# SH3_-_CONNECTORS_2.net
KiCad netlist of a schematic drawn in Altium Designer
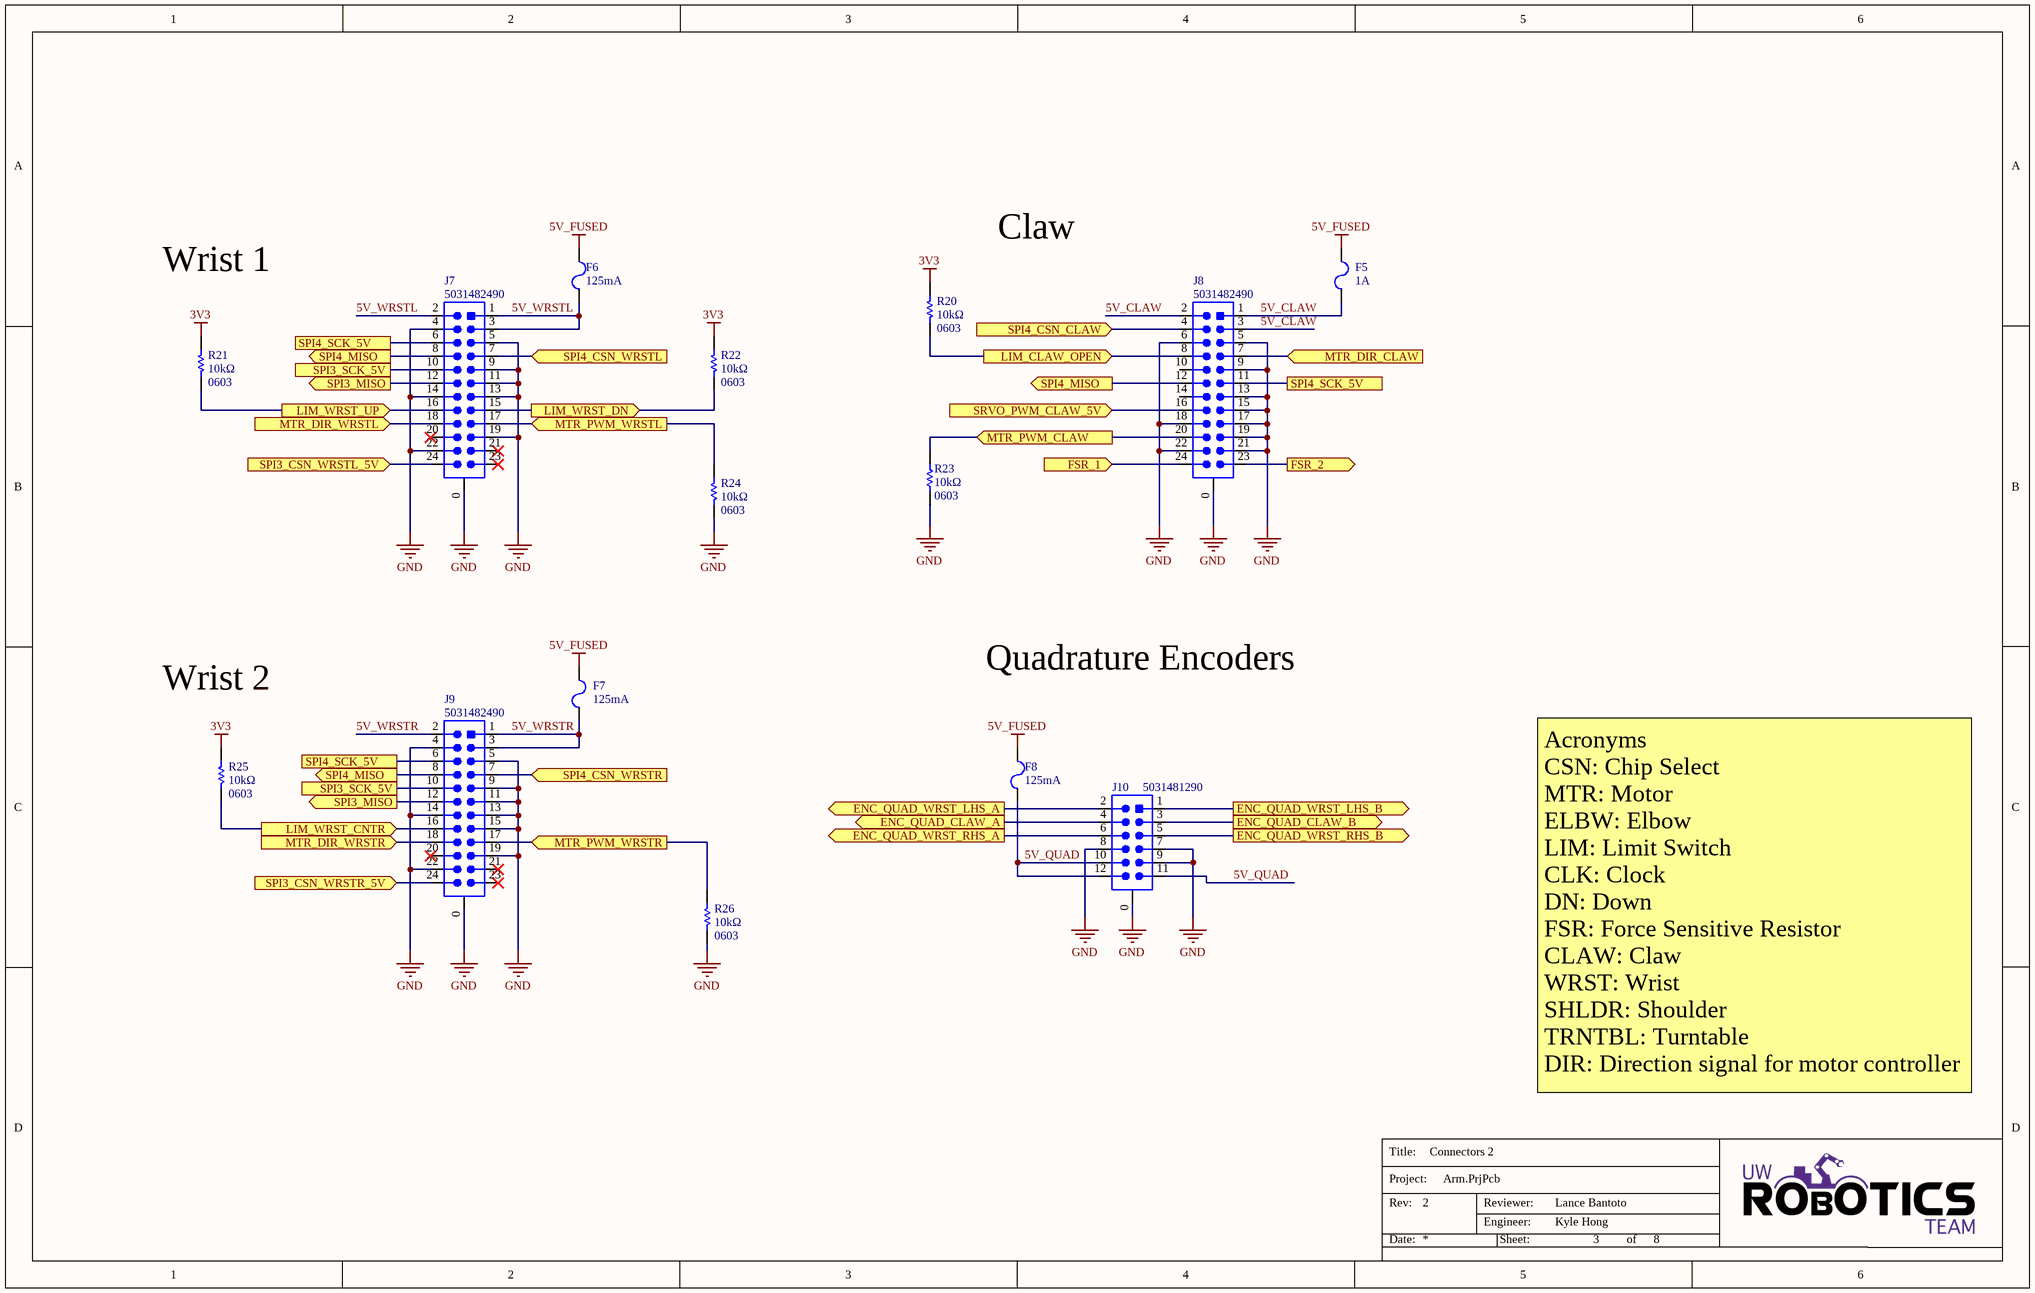
[diagram p0: SH3 - CONNECTORS_2.SchDoc]

(export (version "E")
  (design (tool "Eeschema 10.0.6"))
  (components
    (comp (ref "F5")
      (value "FUSE_1A_1206")
      (footprint "FUSE_1206")
      (description "FUSE BOARD MOUNT 1A 125VAC 63VDC")
      (fields (field (name "CURRENT RATING") "1A"))
      (libsource (lib "UWRT_Schematic_Library_2020") (part "FUSE_1A_1206"))
    )
    (comp (ref "F6")
      (value "FUSE_125mA_1206")
      (footprint "FUSE_1206")
      (description "FUSE BOARD MNT 125MA 125VAC/VDC")
      (fields (field (name "CURRENT RATING") "125mA"))
      (libsource (lib "UWRT_Schematic_Library_2020") (part "FUSE_125mA_1206"))
    )
    (comp (ref "F7")
      (value "FUSE_125mA_1206")
      (footprint "FUSE_1206")
      (description "FUSE BOARD MNT 125MA 125VAC/VDC")
      (fields (field (name "CURRENT RATING") "125mA"))
      (libsource (lib "UWRT_Schematic_Library_2020") (part "FUSE_125mA_1206"))
    )
    (comp (ref "F8")
      (value "FUSE_125mA_1206")
      (footprint "FUSE_1206")
      (description "FUSE BOARD MNT 125MA 125VAC/VDC")
      (fields (field (name "CURRENT RATING") "125mA"))
      (libsource (lib "UWRT_Schematic_Library_2020") (part "FUSE_125mA_1206"))
    )
    (comp (ref "J7")
      (value "CON_12x2M_SM_RA")
      (footprint "MOLEX-5031482490")
      (description "CONN HEADER SMD RIGHT ANGLE 1.5MM PITCH")
      (fields (field (name "MANUFACTURER PART NUMBER 1") "5031482490"))
      (libsource (lib "UWRT_Schematic_Library_2020") (part "CON_12x2M_SM_RA"))
    )
    (comp (ref "J8")
      (value "CON_12x2M_SM_RA")
      (footprint "MOLEX-5031482490")
      (description "CONN HEADER SMD RIGHT ANGLE 1.5MM PITCH")
      (fields (field (name "MANUFACTURER PART NUMBER 1") "5031482490"))
      (libsource (lib "UWRT_Schematic_Library_2020") (part "CON_12x2M_SM_RA"))
    )
    (comp (ref "J9")
      (value "CON_12x2M_SM_RA")
      (footprint "MOLEX-5031482490")
      (description "CONN HEADER SMD RIGHT ANGLE 1.5MM PITCH")
      (fields (field (name "MANUFACTURER PART NUMBER 1") "5031482490"))
      (libsource (lib "UWRT_Schematic_Library_2020") (part "CON_12x2M_SM_RA"))
    )
    (comp (ref "J10")
      (value "CON_6x2M_SM_RA")
      (footprint "MOLEX-5031481290")
      (description "CONN HEADER SMD RIGHT ANGLE 1.5MM PITCH")
      (fields (field (name "MANUFACTURER PART NUMBER 1") "5031481290"))
      (libsource (lib "UWRT_Schematic_Library_2020") (part "CON_6x2M_SM_RA"))
    )
    (comp (ref "R20")
      (value "10kΩ")
      (footprint "RESC0603")
      (description "RES 10K OHM 5% 1/10W 0603")
      (fields (field (name "PACKAGE/FOOTPRINT") "0603") (field (name "Comment") "RES_10kΩ_0603_5%"))
      (libsource (lib "UWRT_Schematic_Library_2020") (part "RES_10kΩ_0603_5%"))
    )
    (comp (ref "R21")
      (value "10kΩ")
      (footprint "RESC0603")
      (description "RES 10K OHM 5% 1/10W 0603")
      (fields (field (name "PACKAGE/FOOTPRINT") "0603") (field (name "Comment") "RES_10kΩ_0603_5%"))
      (libsource (lib "UWRT_Schematic_Library_2020") (part "RES_10kΩ_0603_5%"))
    )
    (comp (ref "R22")
      (value "10kΩ")
      (footprint "RESC0603")
      (description "RES 10K OHM 5% 1/10W 0603")
      (fields (field (name "PACKAGE/FOOTPRINT") "0603") (field (name "Comment") "RES_10kΩ_0603_5%"))
      (libsource (lib "UWRT_Schematic_Library_2020") (part "RES_10kΩ_0603_5%"))
    )
    (comp (ref "R23")
      (value "10kΩ")
      (footprint "RESC0603")
      (description "RES 10K OHM 5% 1/10W 0603")
      (fields (field (name "PACKAGE/FOOTPRINT") "0603") (field (name "Comment") "RES_10kΩ_0603_5%"))
      (libsource (lib "UWRT_Schematic_Library_2020") (part "RES_10kΩ_0603_5%"))
    )
    (comp (ref "R24")
      (value "10kΩ")
      (footprint "RESC0603")
      (description "RES 10K OHM 5% 1/10W 0603")
      (fields (field (name "PACKAGE/FOOTPRINT") "0603") (field (name "Comment") "RES_10kΩ_0603_5%"))
      (libsource (lib "UWRT_Schematic_Library_2020") (part "RES_10kΩ_0603_5%"))
    )
    (comp (ref "R25")
      (value "10kΩ")
      (footprint "RESC0603")
      (description "RES 10K OHM 5% 1/10W 0603")
      (fields (field (name "PACKAGE/FOOTPRINT") "0603") (field (name "Comment") "RES_10kΩ_0603_5%"))
      (libsource (lib "UWRT_Schematic_Library_2020") (part "RES_10kΩ_0603_5%"))
    )
    (comp (ref "R26")
      (value "10kΩ")
      (footprint "RESC0603")
      (description "RES 10K OHM 5% 1/10W 0603")
      (fields (field (name "PACKAGE/FOOTPRINT") "0603") (field (name "Comment") "RES_10kΩ_0603_5%"))
      (libsource (lib "UWRT_Schematic_Library_2020") (part "RES_10kΩ_0603_5%"))
    )
  )
  (nets
    (net (code "1") (name "/5V_CLAW") (class "Default")
      (node (ref "F5") (pin "1") (pinfunction "1_1") (pintype "passive"))
      (node (ref "J8") (pin "1") (pinfunction "1_1") (pintype "passive"))
      (node (ref "J8") (pin "2") (pinfunction "2_2") (pintype "passive"))
      (node (ref "J8") (pin "3") (pinfunction "3_3") (pintype "passive"))
    )
    (net (code "2") (name "/5V_QUAD") (class "Default")
      (node (ref "F8") (pin "1") (pinfunction "1_1") (pintype "passive"))
      (node (ref "J10") (pin "10") (pinfunction "10_10") (pintype "passive"))
      (node (ref "J10") (pin "11") (pinfunction "11_11") (pintype "passive"))
      (node (ref "J10") (pin "12") (pinfunction "12_12") (pintype "passive"))
    )
    (net (code "3") (name "/5V_WRSTL") (class "Default")
      (node (ref "F6") (pin "1") (pinfunction "1_1") (pintype "passive"))
      (node (ref "J7") (pin "1") (pinfunction "1_1") (pintype "passive"))
      (node (ref "J7") (pin "2") (pinfunction "2_2") (pintype "passive"))
      (node (ref "J7") (pin "3") (pinfunction "3_3") (pintype "passive"))
    )
    (net (code "4") (name "/5V_WRSTR") (class "Default")
      (node (ref "F7") (pin "1") (pinfunction "1_1") (pintype "passive"))
      (node (ref "J9") (pin "1") (pinfunction "1_1") (pintype "passive"))
      (node (ref "J9") (pin "2") (pinfunction "2_2") (pintype "passive"))
      (node (ref "J9") (pin "3") (pinfunction "3_3") (pintype "passive"))
    )
    (net (code "5") (name "/ENC_QUAD_CLAW_A") (class "Default")
      (node (ref "J10") (pin "4") (pinfunction "4_4") (pintype "passive"))
    )
    (net (code "6") (name "/ENC_QUAD_CLAW_B") (class "Default")
      (node (ref "J10") (pin "3") (pinfunction "3_3") (pintype "passive"))
    )
    (net (code "7") (name "/ENC_QUAD_WRST_LHS_A") (class "Default")
      (node (ref "J10") (pin "2") (pinfunction "2_2") (pintype "passive"))
    )
    (net (code "8") (name "/ENC_QUAD_WRST_LHS_B") (class "Default")
      (node (ref "J10") (pin "1") (pinfunction "1_1") (pintype "passive"))
    )
    (net (code "9") (name "/ENC_QUAD_WRST_RHS_A") (class "Default")
      (node (ref "J10") (pin "6") (pinfunction "6_6") (pintype "passive"))
    )
    (net (code "10") (name "/ENC_QUAD_WRST_RHS_B") (class "Default")
      (node (ref "J10") (pin "5") (pinfunction "5_5") (pintype "passive"))
    )
    (net (code "11") (name "/FSR_1") (class "Default")
      (node (ref "J8") (pin "24") (pinfunction "24_24") (pintype "passive"))
    )
    (net (code "12") (name "/FSR_2") (class "Default")
      (node (ref "J8") (pin "23") (pinfunction "23_23") (pintype "passive"))
    )
    (net (code "13") (name "/LIM_CLAW_OPEN") (class "Default")
      (node (ref "J8") (pin "8") (pinfunction "8_8") (pintype "passive"))
      (node (ref "R20") (pin "1") (pinfunction "1_1") (pintype "passive"))
    )
    (net (code "14") (name "/LIM_WRST_CNTR") (class "Default")
      (node (ref "J9") (pin "16") (pinfunction "16_16") (pintype "passive"))
      (node (ref "R25") (pin "1") (pinfunction "1_1") (pintype "passive"))
    )
    (net (code "15") (name "/LIM_WRST_DN") (class "Default")
      (node (ref "J7") (pin "15") (pinfunction "15_15") (pintype "passive"))
      (node (ref "R22") (pin "1") (pinfunction "1_1") (pintype "passive"))
    )
    (net (code "16") (name "/LIM_WRST_UP") (class "Default")
      (node (ref "J7") (pin "16") (pinfunction "16_16") (pintype "passive"))
      (node (ref "R21") (pin "1") (pinfunction "1_1") (pintype "passive"))
    )
    (net (code "17") (name "/MTR_DIR_CLAW") (class "Default")
      (node (ref "J8") (pin "7") (pinfunction "7_7") (pintype "passive"))
    )
    (net (code "18") (name "/MTR_DIR_WRSTL") (class "Default")
      (node (ref "J7") (pin "18") (pinfunction "18_18") (pintype "passive"))
    )
    (net (code "19") (name "/MTR_DIR_WRSTR") (class "Default")
      (node (ref "J9") (pin "18") (pinfunction "18_18") (pintype "passive"))
    )
    (net (code "20") (name "/MTR_PWM_CLAW") (class "Default")
      (node (ref "J8") (pin "20") (pinfunction "20_20") (pintype "passive"))
      (node (ref "R23") (pin "2") (pinfunction "2_2") (pintype "passive"))
    )
    (net (code "21") (name "/MTR_PWM_WRSTL") (class "Default")
      (node (ref "J7") (pin "17") (pinfunction "17_17") (pintype "passive"))
      (node (ref "R24") (pin "2") (pinfunction "2_2") (pintype "passive"))
    )
    (net (code "22") (name "/MTR_PWM_WRSTR") (class "Default")
      (node (ref "J9") (pin "17") (pinfunction "17_17") (pintype "passive"))
      (node (ref "R26") (pin "2") (pinfunction "2_2") (pintype "passive"))
    )
    (net (code "23") (name "/SPI3_CSN_WRSTL_5V") (class "Default")
      (node (ref "J7") (pin "24") (pinfunction "24_24") (pintype "passive"))
    )
    (net (code "24") (name "/SPI3_CSN_WRSTR_5V") (class "Default")
      (node (ref "J9") (pin "24") (pinfunction "24_24") (pintype "passive"))
    )
    (net (code "25") (name "/SPI3_MISO") (class "Default")
      (node (ref "J7") (pin "12") (pinfunction "12_12") (pintype "passive"))
      (node (ref "J9") (pin "12") (pinfunction "12_12") (pintype "passive"))
    )
    (net (code "26") (name "/SPI3_SCK_5V") (class "Default")
      (node (ref "J7") (pin "10") (pinfunction "10_10") (pintype "passive"))
      (node (ref "J9") (pin "10") (pinfunction "10_10") (pintype "passive"))
    )
    (net (code "27") (name "/SPI4_CSN_CLAW") (class "Default")
      (node (ref "J8") (pin "4") (pinfunction "4_4") (pintype "passive"))
    )
    (net (code "28") (name "/SPI4_CSN_WRSTL") (class "Default")
      (node (ref "J7") (pin "7") (pinfunction "7_7") (pintype "passive"))
    )
    (net (code "29") (name "/SPI4_CSN_WRSTR") (class "Default")
      (node (ref "J9") (pin "7") (pinfunction "7_7") (pintype "passive"))
    )
    (net (code "30") (name "/SPI4_MISO") (class "Default")
      (node (ref "J7") (pin "8") (pinfunction "8_8") (pintype "passive"))
      (node (ref "J8") (pin "12") (pinfunction "12_12") (pintype "passive"))
      (node (ref "J9") (pin "8") (pinfunction "8_8") (pintype "passive"))
    )
    (net (code "31") (name "/SPI4_SCK_5V") (class "Default")
      (node (ref "J7") (pin "6") (pinfunction "6_6") (pintype "passive"))
      (node (ref "J8") (pin "11") (pinfunction "11_11") (pintype "passive"))
      (node (ref "J9") (pin "6") (pinfunction "6_6") (pintype "passive"))
    )
    (net (code "32") (name "/SRVO_PWM_CLAW_5V") (class "Default")
      (node (ref "J8") (pin "16") (pinfunction "16_16") (pintype "passive"))
    )
    (net (code "33") (name "3V3") (class "Default")
      (node (ref "R20") (pin "2") (pinfunction "2_2") (pintype "passive"))
      (node (ref "R21") (pin "2") (pinfunction "2_2") (pintype "passive"))
      (node (ref "R22") (pin "2") (pinfunction "2_2") (pintype "passive"))
      (node (ref "R25") (pin "2") (pinfunction "2_2") (pintype "passive"))
    )
    (net (code "34") (name "5V_FUSED") (class "Default")
      (node (ref "F5") (pin "2") (pinfunction "2_2") (pintype "passive"))
      (node (ref "F6") (pin "2") (pinfunction "2_2") (pintype "passive"))
      (node (ref "F7") (pin "2") (pinfunction "2_2") (pintype "passive"))
      (node (ref "F8") (pin "2") (pinfunction "2_2") (pintype "passive"))
    )
    (net (code "35") (name "GND") (class "Default")
      (node (ref "J10") (pin "0") (pinfunction "0_0") (pintype "passive"))
      (node (ref "J10") (pin "7") (pinfunction "7_7") (pintype "passive"))
      (node (ref "J10") (pin "8") (pinfunction "8_8") (pintype "passive"))
      (node (ref "J10") (pin "9") (pinfunction "9_9") (pintype "passive"))
      (node (ref "J7") (pin "0") (pinfunction "0_0") (pintype "passive"))
      (node (ref "J7") (pin "11") (pinfunction "11_11") (pintype "passive"))
      (node (ref "J7") (pin "13") (pinfunction "13_13") (pintype "passive"))
      (node (ref "J7") (pin "14") (pinfunction "14_14") (pintype "passive"))
      (node (ref "J7") (pin "19") (pinfunction "19_19") (pintype "passive"))
      (node (ref "J7") (pin "22") (pinfunction "22_22") (pintype "passive"))
      (node (ref "J7") (pin "4") (pinfunction "4_4") (pintype "passive"))
      (node (ref "J7") (pin "5") (pinfunction "5_5") (pintype "passive"))
      (node (ref "J7") (pin "9") (pinfunction "9_9") (pintype "passive"))
      (node (ref "J8") (pin "0") (pinfunction "0_0") (pintype "passive"))
      (node (ref "J8") (pin "13") (pinfunction "13_13") (pintype "passive"))
      (node (ref "J8") (pin "15") (pinfunction "15_15") (pintype "passive"))
      (node (ref "J8") (pin "17") (pinfunction "17_17") (pintype "passive"))
      (node (ref "J8") (pin "18") (pinfunction "18_18") (pintype "passive"))
      (node (ref "J8") (pin "19") (pinfunction "19_19") (pintype "passive"))
      (node (ref "J8") (pin "21") (pinfunction "21_21") (pintype "passive"))
      (node (ref "J8") (pin "22") (pinfunction "22_22") (pintype "passive"))
      (node (ref "J8") (pin "5") (pinfunction "5_5") (pintype "passive"))
      (node (ref "J8") (pin "6") (pinfunction "6_6") (pintype "passive"))
      (node (ref "J8") (pin "9") (pinfunction "9_9") (pintype "passive"))
      (node (ref "J9") (pin "0") (pinfunction "0_0") (pintype "passive"))
      (node (ref "J9") (pin "11") (pinfunction "11_11") (pintype "passive"))
      (node (ref "J9") (pin "13") (pinfunction "13_13") (pintype "passive"))
      (node (ref "J9") (pin "14") (pinfunction "14_14") (pintype "passive"))
      (node (ref "J9") (pin "15") (pinfunction "15_15") (pintype "passive"))
      (node (ref "J9") (pin "19") (pinfunction "19_19") (pintype "passive"))
      (node (ref "J9") (pin "22") (pinfunction "22_22") (pintype "passive"))
      (node (ref "J9") (pin "4") (pinfunction "4_4") (pintype "passive"))
      (node (ref "J9") (pin "5") (pinfunction "5_5") (pintype "passive"))
      (node (ref "J9") (pin "9") (pinfunction "9_9") (pintype "passive"))
      (node (ref "R23") (pin "1") (pinfunction "1_1") (pintype "passive"))
      (node (ref "R24") (pin "1") (pinfunction "1_1") (pintype "passive"))
      (node (ref "R26") (pin "1") (pinfunction "1_1") (pintype "passive"))
    )
    (net (code "36") (name "unconnected-(J7-Pad20)") (class "Default")
      (node (ref "J7") (pin "20") (pinfunction "20_20") (pintype "passive+no_connect"))
    )
    (net (code "37") (name "unconnected-(J7-Pad21)") (class "Default")
      (node (ref "J7") (pin "21") (pinfunction "21_21") (pintype "passive+no_connect"))
    )
    (net (code "38") (name "unconnected-(J7-Pad23)") (class "Default")
      (node (ref "J7") (pin "23") (pinfunction "23_23") (pintype "passive+no_connect"))
    )
    (net (code "39") (name "unconnected-(J8-Pad10)") (class "Default")
      (node (ref "J8") (pin "10") (pinfunction "10_10") (pintype "passive"))
    )
    (net (code "40") (name "unconnected-(J8-Pad14)") (class "Default")
      (node (ref "J8") (pin "14") (pinfunction "14_14") (pintype "passive"))
    )
    (net (code "41") (name "unconnected-(J9-Pad20)") (class "Default")
      (node (ref "J9") (pin "20") (pinfunction "20_20") (pintype "passive+no_connect"))
    )
    (net (code "42") (name "unconnected-(J9-Pad21)") (class "Default")
      (node (ref "J9") (pin "21") (pinfunction "21_21") (pintype "passive+no_connect"))
    )
    (net (code "43") (name "unconnected-(J9-Pad23)") (class "Default")
      (node (ref "J9") (pin "23") (pinfunction "23_23") (pintype "passive+no_connect"))
    )
  )
)
